# Trinket_Altium_File.net
KiCad netlist of a schematic drawn in Altium Designer
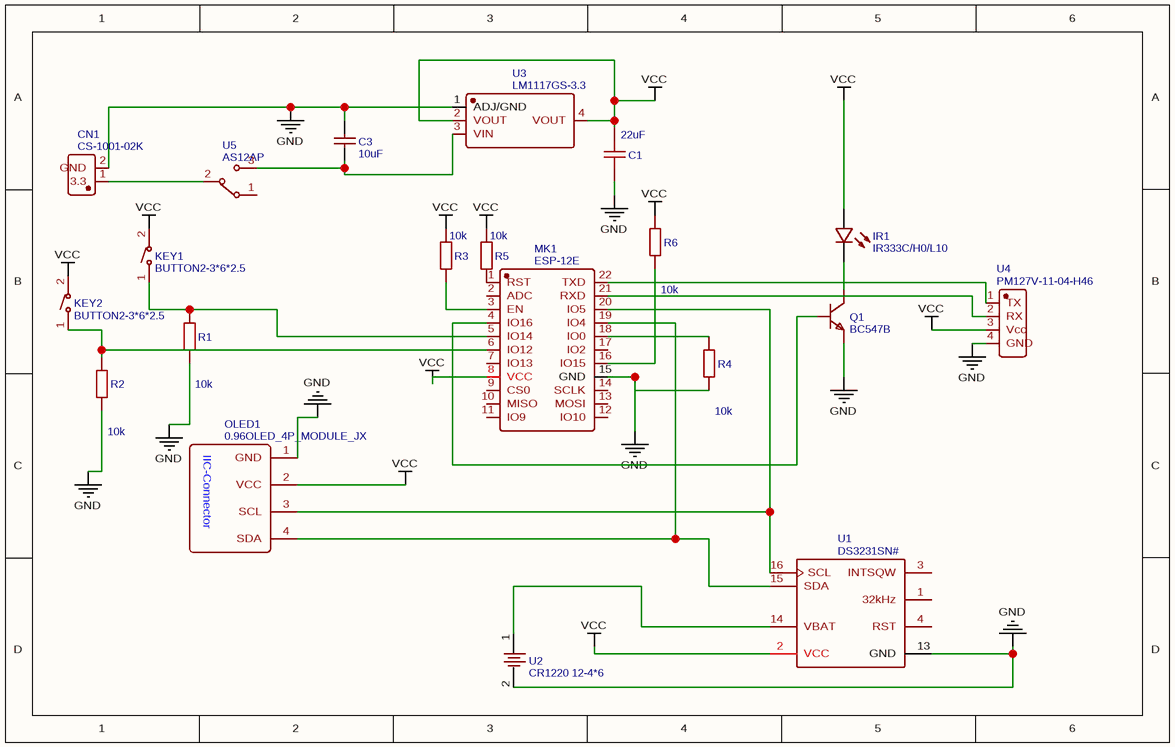
[diagram p0: Trinket_Altium_File.schdoc]

(export (version "E")
  (design (tool "Eeschema 10.0.6"))
  (components
    (comp (ref "C1")
      (value "22uF")
      (fields
        (field (name "MANUFACTURER") "YAGEO")
        (field (name "MANUFACTURER PART") "CC0805KKX5R5BB226")
        (field (name "CONTRIBUTOR") "LCSC")
      )
      (libsource (lib "altium-import") (part "root_0_22uF_"))
    )
    (comp (ref "C3")
      (value "10uF")
      (fields
        (field (name "MANUFACTURER") "YAGEO")
        (field (name "MANUFACTURER PART") "CC1206KKX5R8BB106")
        (field (name "CONTRIBUTOR") "LCSC")
      )
      (libsource (lib "altium-import") (part "root_1_10uF_"))
    )
    (comp (ref "CN1")
      (value "CS-1001-02K")
      (fields (field (name "MANUFACTURER") "CST(永丰盈)") (field (name "CONTRIBUTOR") "LCSC"))
      (libsource (lib "altium-import") (part "root_2_CS-1001-02K_"))
    )
    (comp (ref "IR1")
      (value "IR333C/H0/L10")
      (fields (field (name "MANUFACTURER") "EVERLIGHT"))
      (libsource (lib "altium-import") (part "root_3_IR333C/H0/L10_"))
    )
    (comp (ref "KEY1")
      (value "BUTTON2-3*6*2.5")
      (fields (field (name "CONTRIBUTOR") "LCSC"))
      (libsource (lib "altium-import") (part "root_1_BUTTON2-3*6*2.5_"))
    )
    (comp (ref "KEY2")
      (value "BUTTON2-3*6*2.5")
      (fields (field (name "CONTRIBUTOR") "LCSC"))
      (libsource (lib "altium-import") (part "root_1_BUTTON2-3*6*2.5_"))
    )
    (comp (ref "MK1")
      (value "ESP-12E")
      (fields (field (name "MANUFACTURER") "Ai-Thinker"))
      (libsource (lib "altium-import") (part "root_0_ESP-12E_"))
    )
    (comp (ref "OLED1")
      (value "0.96OLED_4P_MODULE_JX")
      (fields (field (name "CONTRIBUTOR") "LCSC"))
      (libsource (lib "altium-import") (part "root_0_0.96OLED_4P_MODULE_JX_"))
    )
    (comp (ref "Q1")
      (value "BC547B")
      (fields (field (name "MANUFACTURER") "LGE") (field (name "CONTRIBUTOR") "LCSC"))
      (libsource (lib "altium-import") (part "root_0_BC547B_"))
    )
    (comp (ref "R1")
      (value "10k")
      (fields
        (field (name "MANUFACTURER") "ResistorToday")
        (field (name "MANUFACTURER PART") "AECR1206F2R00T9")
        (field (name "CONTRIBUTOR") "LCSC")
      )
      (libsource (lib "altium-import") (part "root_1_10k_"))
    )
    (comp (ref "R2")
      (value "10k")
      (fields
        (field (name "MANUFACTURER") "ResistorToday")
        (field (name "MANUFACTURER PART") "AECR1206F2R00T9")
        (field (name "CONTRIBUTOR") "LCSC")
      )
      (libsource (lib "altium-import") (part "root_1_10k_"))
    )
    (comp (ref "R3")
      (value "10k")
      (fields
        (field (name "MANUFACTURER") "ResistorToday")
        (field (name "MANUFACTURER PART") "AECR1206F2R00T9")
        (field (name "CONTRIBUTOR") "LCSC")
      )
      (libsource (lib "altium-import") (part "root_1_10k_"))
    )
    (comp (ref "R4")
      (value "10k")
      (fields
        (field (name "MANUFACTURER") "ResistorToday")
        (field (name "MANUFACTURER PART") "AECR1206F2R00T9")
        (field (name "CONTRIBUTOR") "LCSC")
      )
      (libsource (lib "altium-import") (part "root_1_10k_"))
    )
    (comp (ref "R5")
      (value "10k")
      (fields
        (field (name "MANUFACTURER") "ResistorToday")
        (field (name "MANUFACTURER PART") "AECR1206F2R00T9")
        (field (name "CONTRIBUTOR") "LCSC")
      )
      (libsource (lib "altium-import") (part "root_1_10k_"))
    )
    (comp (ref "R6")
      (value "10k")
      (fields
        (field (name "MANUFACTURER") "ResistorToday")
        (field (name "MANUFACTURER PART") "AECR1206F2R00T9")
        (field (name "CONTRIBUTOR") "LCSC")
      )
      (libsource (lib "altium-import") (part "root_1_10k_"))
    )
    (comp (ref "U1")
      (value "DS3231SN#")
      (fields
        (field (name "MANUFACTURER") "MAXIM")
        (field (name "MANUFACTURER PART") "DS3231SN")
        (field (name "SUBPART_NO") "1")
      )
      (libsource (lib "altium-import") (part "root_0_DS3231SN#_"))
    )
    (comp (ref "U2")
      (value "CR1220 12-4*6")
      (fields (field (name "MANUFACTURER") "Q&J") (field (name "CONTRIBUTOR") "LCSC"))
      (libsource (lib "altium-import") (part "root_3_CR1220 12-4*6_"))
    )
    (comp (ref "U3")
      (value "LM1117GS-3.3")
      (fields (field (name "MANUFACTURER") "HTC Korea TAEJIN Tech") (field (name "CONTRIBUTOR") "LCSC"))
      (libsource (lib "altium-import") (part "root_0_LM1117GS-3.3_"))
    )
    (comp (ref "U4")
      (value "PM127V-11-04-H46")
      (fields (field (name "MANUFACTURER") "XFCN(兴飞)") (field (name "CONTRIBUTOR") "lcsc"))
      (libsource (lib "altium-import") (part "root_0_PM127V-11-04-H46_"))
    )
    (comp (ref "U5")
      (value "AS12AP")
      (fields (field (name "MANUFACTURER") "NKK Switches") (field (name "CONTRIBUTOR") "lcsc"))
      (libsource (lib "altium-import") (part "root_1_AS12AP_"))
    )
  )
  (nets
    (net (code "1") (name "GND") (class "Default")
      (node (ref "C1") (pin "1") (pinfunction "1_1") (pintype "passive"))
      (node (ref "C3") (pin "2") (pinfunction "2_2") (pintype "passive"))
      (node (ref "CN1") (pin "2") (pinfunction "GND_2") (pintype "passive"))
      (node (ref "MK1") (pin "15") (pinfunction "GND_15") (pintype "passive"))
      (node (ref "OLED1") (pin "1") (pinfunction "GND_1") (pintype "passive"))
      (node (ref "Q1") (pin "3") (pinfunction "E_3") (pintype "passive"))
      (node (ref "R1") (pin "1") (pinfunction "1_1") (pintype "passive"))
      (node (ref "R2") (pin "1") (pinfunction "1_1") (pintype "passive"))
      (node (ref "R4") (pin "1") (pinfunction "1_1") (pintype "passive"))
      (node (ref "U1") (pin "13") (pinfunction "GND_13") (pintype "passive"))
      (node (ref "U2") (pin "2") (pinfunction "2_2") (pintype "passive"))
      (node (ref "U3") (pin "1") (pinfunction "ADJ/GND_1") (pintype "passive"))
      (node (ref "U4") (pin "4") (pinfunction "GND_4") (pintype "passive"))
    )
    (net (code "2") (name "Net-(CN1-3.3)") (class "Default")
      (node (ref "CN1") (pin "1") (pinfunction "3.3_1") (pintype "passive"))
      (node (ref "U5") (pin "2") (pinfunction "2_2") (pintype "passive"))
    )
    (net (code "3") (name "Net-(IR1-C)") (class "Default")
      (node (ref "IR1") (pin "2") (pinfunction "C_2") (pintype "passive"))
      (node (ref "Q1") (pin "1") (pinfunction "C_1") (pintype "passive"))
    )
    (net (code "4") (name "Net-(MK1-EN)") (class "Default")
      (node (ref "MK1") (pin "3") (pinfunction "EN_3") (pintype "passive"))
      (node (ref "R3") (pin "1") (pinfunction "1_1") (pintype "passive"))
    )
    (net (code "5") (name "Net-(MK1-IO0)") (class "Default")
      (node (ref "MK1") (pin "18") (pinfunction "IO0_18") (pintype "passive"))
      (node (ref "R4") (pin "2") (pinfunction "2_2") (pintype "passive"))
    )
    (net (code "6") (name "Net-(MK1-IO4)") (class "Default")
      (node (ref "MK1") (pin "19") (pinfunction "IO4_19") (pintype "passive"))
      (node (ref "OLED1") (pin "4") (pinfunction "SDA_4") (pintype "passive"))
      (node (ref "U1") (pin "15") (pinfunction "SDA_15") (pintype "passive"))
    )
    (net (code "7") (name "Net-(MK1-IO5)") (class "Default")
      (node (ref "MK1") (pin "20") (pinfunction "IO5_20") (pintype "passive"))
      (node (ref "OLED1") (pin "3") (pinfunction "SCL_3") (pintype "passive"))
      (node (ref "U1") (pin "16") (pinfunction "SCL_16") (pintype "passive"))
    )
    (net (code "8") (name "Net-(MK1-IO12)") (class "Default")
      (node (ref "KEY2") (pin "1") (pinfunction "1_1") (pintype "passive"))
      (node (ref "MK1") (pin "6") (pinfunction "IO12_6") (pintype "passive"))
      (node (ref "R2") (pin "2") (pinfunction "2_2") (pintype "passive"))
    )
    (net (code "9") (name "Net-(MK1-IO14)") (class "Default")
      (node (ref "KEY1") (pin "1") (pinfunction "1_1") (pintype "passive"))
      (node (ref "MK1") (pin "5") (pinfunction "IO14_5") (pintype "passive"))
      (node (ref "R1") (pin "2") (pinfunction "2_2") (pintype "passive"))
    )
    (net (code "10") (name "Net-(MK1-IO15)") (class "Default")
      (node (ref "MK1") (pin "16") (pinfunction "IO15_16") (pintype "passive"))
      (node (ref "R6") (pin "1") (pinfunction "1_1") (pintype "passive"))
    )
    (net (code "11") (name "Net-(MK1-IO16)") (class "Default")
      (node (ref "MK1") (pin "4") (pinfunction "IO16_4") (pintype "passive"))
      (node (ref "Q1") (pin "2") (pinfunction "B_2") (pintype "passive"))
    )
    (net (code "12") (name "Net-(MK1-RST)") (class "Default")
      (node (ref "MK1") (pin "1") (pinfunction "RST_1") (pintype "passive"))
      (node (ref "R5") (pin "1") (pinfunction "1_1") (pintype "passive"))
    )
    (net (code "13") (name "Net-(MK1-RXD)") (class "Default")
      (node (ref "MK1") (pin "21") (pinfunction "RXD_21") (pintype "passive"))
      (node (ref "U4") (pin "2") (pinfunction "RX_2") (pintype "passive"))
    )
    (net (code "14") (name "Net-(MK1-TXD)") (class "Default")
      (node (ref "MK1") (pin "22") (pinfunction "TXD_22") (pintype "passive"))
      (node (ref "U4") (pin "1") (pinfunction "TX_1") (pintype "passive"))
    )
    (net (code "15") (name "Net-(U1-VBAT)") (class "Default")
      (node (ref "U1") (pin "14") (pinfunction "VBAT_14") (pintype "passive"))
      (node (ref "U2") (pin "1") (pinfunction "1_1") (pintype "passive"))
    )
    (net (code "16") (name "Net-(U3-VIN)") (class "Default")
      (node (ref "C3") (pin "1") (pinfunction "1_1") (pintype "passive"))
      (node (ref "U3") (pin "3") (pinfunction "VIN_3") (pintype "passive"))
      (node (ref "U5") (pin "3") (pinfunction "3_3") (pintype "passive"))
    )
    (net (code "17") (name "VCC") (class "Default")
      (node (ref "C1") (pin "2") (pinfunction "2_2") (pintype "passive"))
      (node (ref "IR1") (pin "1") (pinfunction "A_1") (pintype "passive"))
      (node (ref "KEY1") (pin "2") (pinfunction "2_2") (pintype "passive"))
      (node (ref "KEY2") (pin "2") (pinfunction "2_2") (pintype "passive"))
      (node (ref "MK1") (pin "8") (pinfunction "VCC_8") (pintype "passive"))
      (node (ref "OLED1") (pin "2") (pinfunction "VCC_2") (pintype "passive"))
      (node (ref "R3") (pin "2") (pinfunction "2_2") (pintype "passive"))
      (node (ref "R5") (pin "2") (pinfunction "2_2") (pintype "passive"))
      (node (ref "R6") (pin "2") (pinfunction "2_2") (pintype "passive"))
      (node (ref "U1") (pin "2") (pinfunction "VCC_2") (pintype "passive"))
      (node (ref "U3") (pin "2") (pinfunction "VOUT_2") (pintype "passive"))
      (node (ref "U3") (pin "4") (pinfunction "VOUT_4") (pintype "passive"))
      (node (ref "U4") (pin "3") (pinfunction "Vcc_3") (pintype "passive"))
    )
    (net (code "18") (name "unconnected-(MK1-ADC-Pad2)") (class "Default")
      (node (ref "MK1") (pin "2") (pinfunction "ADC_2") (pintype "passive"))
    )
    (net (code "19") (name "unconnected-(MK1-CS0-Pad9)") (class "Default")
      (node (ref "MK1") (pin "9") (pinfunction "CS0_9") (pintype "passive"))
    )
    (net (code "20") (name "unconnected-(MK1-IO2-Pad17)") (class "Default")
      (node (ref "MK1") (pin "17") (pinfunction "IO2_17") (pintype "passive"))
    )
    (net (code "21") (name "unconnected-(MK1-IO9-Pad11)") (class "Default")
      (node (ref "MK1") (pin "11") (pinfunction "IO9_11") (pintype "passive"))
    )
    (net (code "22") (name "unconnected-(MK1-IO10-Pad12)") (class "Default")
      (node (ref "MK1") (pin "12") (pinfunction "IO10_12") (pintype "passive"))
    )
    (net (code "23") (name "unconnected-(MK1-IO13-Pad7)") (class "Default")
      (node (ref "MK1") (pin "7") (pinfunction "IO13_7") (pintype "passive"))
    )
    (net (code "24") (name "unconnected-(MK1-MISO-Pad10)") (class "Default")
      (node (ref "MK1") (pin "10") (pinfunction "MISO_10") (pintype "passive"))
    )
    (net (code "25") (name "unconnected-(MK1-MOSI-Pad13)") (class "Default")
      (node (ref "MK1") (pin "13") (pinfunction "MOSI_13") (pintype "passive"))
    )
    (net (code "26") (name "unconnected-(MK1-SCLK-Pad14)") (class "Default")
      (node (ref "MK1") (pin "14") (pinfunction "SCLK_14") (pintype "passive"))
    )
    (net (code "27") (name "unconnected-(U1-32kHz-Pad1)") (class "Default")
      (node (ref "U1") (pin "1") (pinfunction "32kHz_1") (pintype "passive"))
    )
    (net (code "28") (name "unconnected-(U1-INTSQW-Pad3)") (class "Default")
      (node (ref "U1") (pin "3") (pinfunction "INTSQW_3") (pintype "passive"))
    )
    (net (code "29") (name "unconnected-(U1-RST-Pad4)") (class "Default")
      (node (ref "U1") (pin "4") (pinfunction "RST_4") (pintype "passive"))
    )
    (net (code "30") (name "unconnected-(U5-Pad1)") (class "Default")
      (node (ref "U5") (pin "1") (pinfunction "1_1") (pintype "passive"))
    )
  )
)
